# DBoard_Conn.net
KiCad netlist of a schematic drawn in Altium Designer
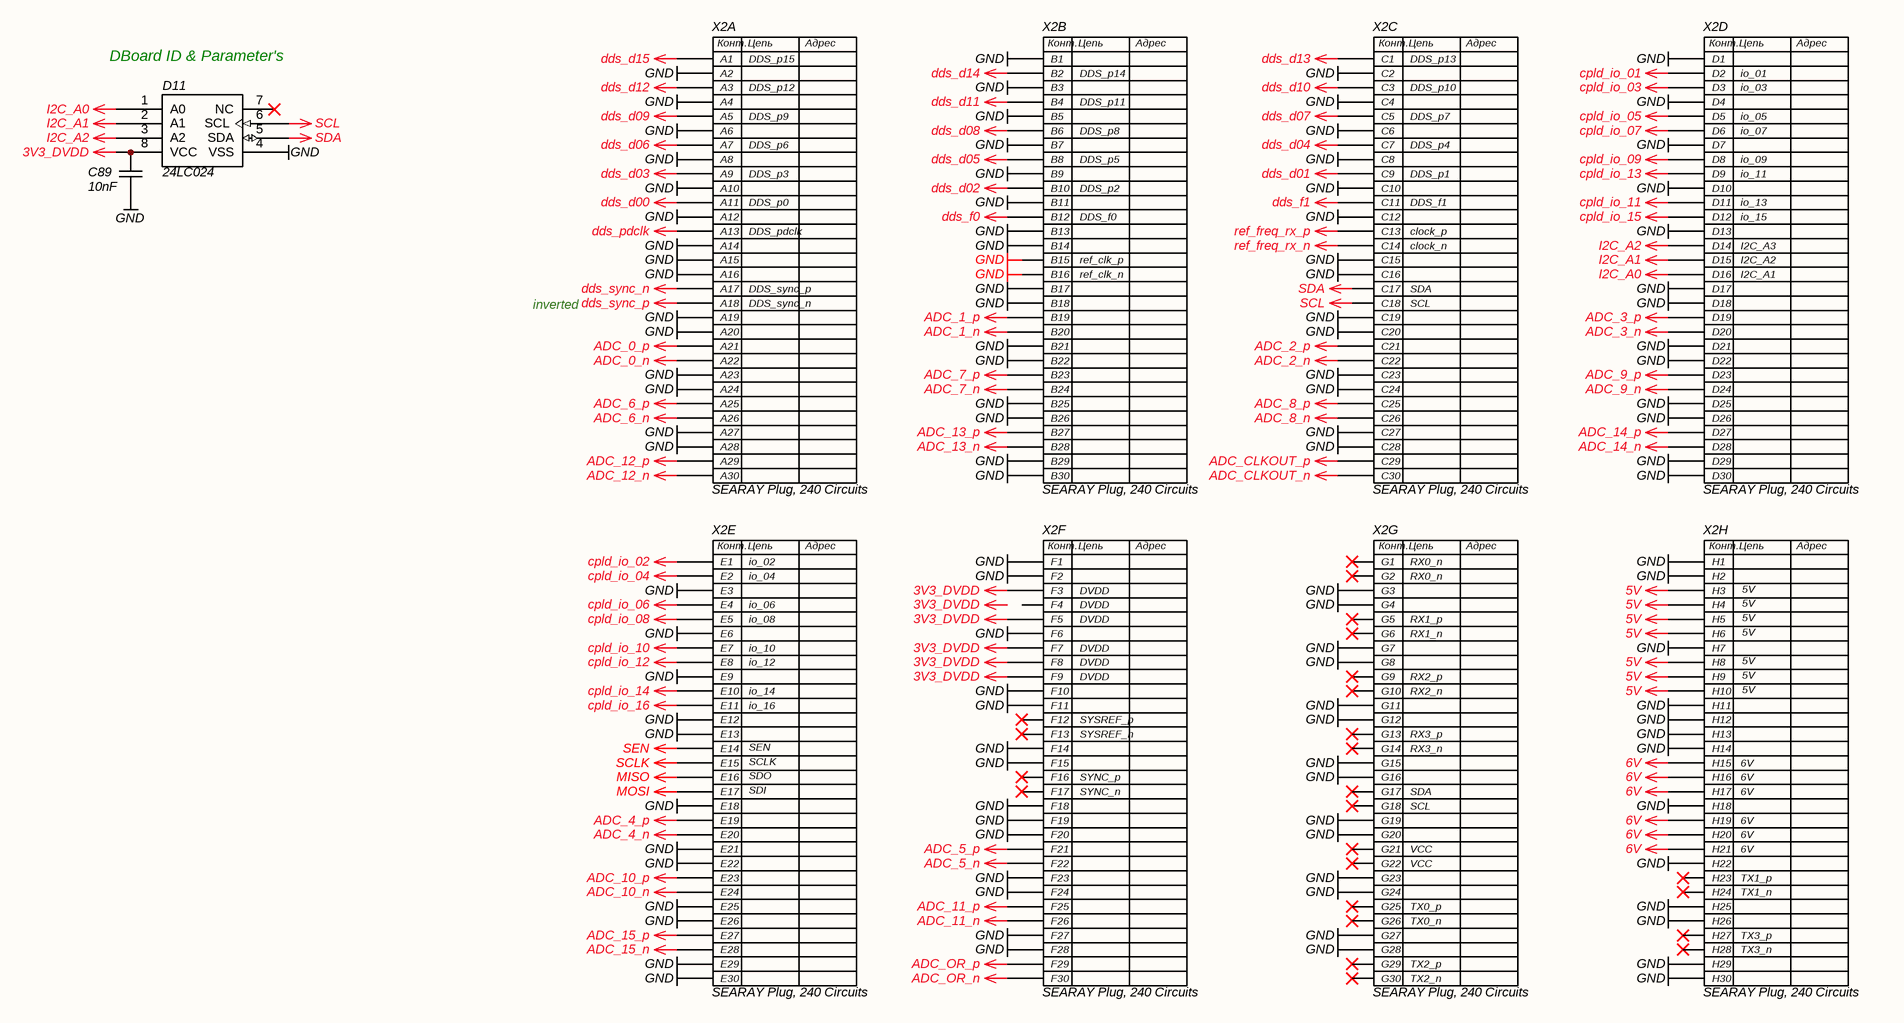
[diagram p0: DBoard_Conn.SchDoc]

(export (version "E")
  (design (tool "Eeschema 10.0.6"))
  (components
    (comp (ref "C89")
      (value "10nF")
      (footprint "C0402")
      (description "SMD Capacitor")
      (fields (field (name "MANUFACTURER") "Murata") (field (name "TOLERANCE") "10%"))
      (libsource (lib "Kintex_SDR") (part "CAP"))
    )
    (comp (ref "D11")
      (value "24LC024")
      (footprint "SOIC_SN8")
      (description "I2C EEPROM")
      (fields (field (name "MANUFACTURER") "Microchip") (field (name "VOLTAGE") "2.5-5.5V"))
      (libsource (lib "Kintex_SDR") (part "24LC024"))
    )
    (comp (ref "X2")
      (value "SEARAY Plug, 240 Circuits")
      (footprint "DBLib:Molex_459703185")
      (description "1.27mm Pitch, SEARAY Plug, 240 Circuits, 2.00mm Unmated Height, 8 Rows, with Pegs")
      (fields (field (name "MANUFACTURER") "Molex"))
      (libsource (lib "DBLib") (part "Molex_SEARAY™ 45970"))
    )
  )
  (nets
    (net (code "42") (name "3V3_DVDD") (class "Default")
      (node (ref "C89") (pin "2") (pinfunction "2_2") (pintype "passive"))
      (node (ref "D11") (pin "8") (pinfunction "VCC_8") (pintype "power_in"))
      (node (ref "X2") (pin "F3") (pinfunction "F3_F3") (pintype "passive"))
      (node (ref "X2") (pin "F5") (pinfunction "F5_F5") (pintype "passive"))
      (node (ref "X2") (pin "F7") (pinfunction "F7_F7") (pintype "passive"))
      (node (ref "X2") (pin "F8") (pinfunction "F8_F8") (pintype "passive"))
      (node (ref "X2") (pin "F9") (pinfunction "F9_F9") (pintype "passive"))
    )
    (net (code "43") (name "5V") (class "Default")
      (node (ref "X2") (pin "H10") (pinfunction "H10_H10") (pintype "passive"))
      (node (ref "X2") (pin "H3") (pinfunction "H3_H3") (pintype "passive"))
      (node (ref "X2") (pin "H4") (pinfunction "H4_H4") (pintype "passive"))
      (node (ref "X2") (pin "H5") (pinfunction "H5_H5") (pintype "passive"))
      (node (ref "X2") (pin "H6") (pinfunction "H6_H6") (pintype "passive"))
      (node (ref "X2") (pin "H8") (pinfunction "H8_H8") (pintype "passive"))
      (node (ref "X2") (pin "H9") (pinfunction "H9_H9") (pintype "passive"))
    )
    (net (code "44") (name "6V") (class "Default")
      (node (ref "X2") (pin "H15") (pinfunction "H15_H15") (pintype "passive"))
      (node (ref "X2") (pin "H16") (pinfunction "H16_H16") (pintype "passive"))
      (node (ref "X2") (pin "H17") (pinfunction "H17_H17") (pintype "passive"))
      (node (ref "X2") (pin "H19") (pinfunction "H19_H19") (pintype "passive"))
      (node (ref "X2") (pin "H20") (pinfunction "H20_H20") (pintype "passive"))
      (node (ref "X2") (pin "H21") (pinfunction "H21_H21") (pintype "passive"))
    )
    (net (code "45") (name "ADC_0_n") (class "Default")
      (node (ref "X2") (pin "A22") (pinfunction "A22_A22") (pintype "passive"))
    )
    (net (code "46") (name "ADC_0_p") (class "Default")
      (node (ref "X2") (pin "A21") (pinfunction "A21_A21") (pintype "passive"))
    )
    (net (code "47") (name "ADC_1_n") (class "Default")
      (node (ref "X2") (pin "B20") (pinfunction "B20_B20") (pintype "passive"))
    )
    (net (code "48") (name "ADC_1_p") (class "Default")
      (node (ref "X2") (pin "B19") (pinfunction "B19_B19") (pintype "passive"))
    )
    (net (code "49") (name "ADC_2_n") (class "Default")
      (node (ref "X2") (pin "C22") (pinfunction "C22_C22") (pintype "passive"))
    )
    (net (code "50") (name "ADC_2_p") (class "Default")
      (node (ref "X2") (pin "C21") (pinfunction "C21_C21") (pintype "passive"))
    )
    (net (code "51") (name "ADC_3_n") (class "Default")
      (node (ref "X2") (pin "D20") (pinfunction "D20_D20") (pintype "passive"))
    )
    (net (code "52") (name "ADC_3_p") (class "Default")
      (node (ref "X2") (pin "D19") (pinfunction "D19_D19") (pintype "passive"))
    )
    (net (code "53") (name "ADC_4_n") (class "Default")
      (node (ref "X2") (pin "E20") (pinfunction "E20_E20") (pintype "passive"))
    )
    (net (code "54") (name "ADC_4_p") (class "Default")
      (node (ref "X2") (pin "E19") (pinfunction "E19_E19") (pintype "passive"))
    )
    (net (code "55") (name "ADC_5_n") (class "Default")
      (node (ref "X2") (pin "F22") (pinfunction "F22_F22") (pintype "passive"))
    )
    (net (code "56") (name "ADC_5_p") (class "Default")
      (node (ref "X2") (pin "F21") (pinfunction "F21_F21") (pintype "passive"))
    )
    (net (code "57") (name "ADC_6_n") (class "Default")
      (node (ref "X2") (pin "A26") (pinfunction "A26_A26") (pintype "passive"))
    )
    (net (code "58") (name "ADC_6_p") (class "Default")
      (node (ref "X2") (pin "A25") (pinfunction "A25_A25") (pintype "passive"))
    )
    (net (code "59") (name "ADC_7_n") (class "Default")
      (node (ref "X2") (pin "B24") (pinfunction "B24_B24") (pintype "passive"))
    )
    (net (code "60") (name "ADC_7_p") (class "Default")
      (node (ref "X2") (pin "B23") (pinfunction "B23_B23") (pintype "passive"))
    )
    (net (code "61") (name "ADC_8_n") (class "Default")
      (node (ref "X2") (pin "C26") (pinfunction "C26_C26") (pintype "passive"))
    )
    (net (code "62") (name "ADC_8_p") (class "Default")
      (node (ref "X2") (pin "C25") (pinfunction "C25_C25") (pintype "passive"))
    )
    (net (code "63") (name "ADC_9_n") (class "Default")
      (node (ref "X2") (pin "D24") (pinfunction "D24_D24") (pintype "passive"))
    )
    (net (code "64") (name "ADC_9_p") (class "Default")
      (node (ref "X2") (pin "D23") (pinfunction "D23_D23") (pintype "passive"))
    )
    (net (code "65") (name "ADC_10_n") (class "Default")
      (node (ref "X2") (pin "E24") (pinfunction "E24_E24") (pintype "passive"))
    )
    (net (code "66") (name "ADC_10_p") (class "Default")
      (node (ref "X2") (pin "E23") (pinfunction "E23_E23") (pintype "passive"))
    )
    (net (code "67") (name "ADC_11_n") (class "Default")
      (node (ref "X2") (pin "F26") (pinfunction "F26_F26") (pintype "passive"))
    )
    (net (code "68") (name "ADC_11_p") (class "Default")
      (node (ref "X2") (pin "F25") (pinfunction "F25_F25") (pintype "passive"))
    )
    (net (code "69") (name "ADC_12_n") (class "Default")
      (node (ref "X2") (pin "A30") (pinfunction "A30_A30") (pintype "passive"))
    )
    (net (code "70") (name "ADC_12_p") (class "Default")
      (node (ref "X2") (pin "A29") (pinfunction "A29_A29") (pintype "passive"))
    )
    (net (code "71") (name "ADC_13_n") (class "Default")
      (node (ref "X2") (pin "B28") (pinfunction "B28_B28") (pintype "passive"))
    )
    (net (code "72") (name "ADC_13_p") (class "Default")
      (node (ref "X2") (pin "B27") (pinfunction "B27_B27") (pintype "passive"))
    )
    (net (code "73") (name "ADC_14_n") (class "Default")
      (node (ref "X2") (pin "D28") (pinfunction "D28_D28") (pintype "passive"))
    )
    (net (code "74") (name "ADC_14_p") (class "Default")
      (node (ref "X2") (pin "D27") (pinfunction "D27_D27") (pintype "passive"))
    )
    (net (code "75") (name "ADC_15_n") (class "Default")
      (node (ref "X2") (pin "E28") (pinfunction "E28_E28") (pintype "passive"))
    )
    (net (code "76") (name "ADC_15_p") (class "Default")
      (node (ref "X2") (pin "E27") (pinfunction "E27_E27") (pintype "passive"))
    )
    (net (code "77") (name "ADC_CLKOUT_n") (class "Default")
      (node (ref "X2") (pin "C30") (pinfunction "C30_C30") (pintype "passive"))
    )
    (net (code "78") (name "ADC_CLKOUT_p") (class "Default")
      (node (ref "X2") (pin "C29") (pinfunction "C29_C29") (pintype "passive"))
    )
    (net (code "79") (name "ADC_OR_n") (class "Default")
      (node (ref "X2") (pin "F30") (pinfunction "F30_F30") (pintype "passive"))
    )
    (net (code "80") (name "ADC_OR_p") (class "Default")
      (node (ref "X2") (pin "F29") (pinfunction "F29_F29") (pintype "passive"))
    )
    (net (code "81") (name "GND") (class "Default")
      (node (ref "C89") (pin "1") (pinfunction "1_1") (pintype "passive"))
      (node (ref "D11") (pin "4") (pinfunction "VSS_4") (pintype "power_in"))
      (node (ref "X2") (pin "A10") (pinfunction "A10_A10") (pintype "passive"))
      (node (ref "X2") (pin "A12") (pinfunction "A12_A12") (pintype "passive"))
      (node (ref "X2") (pin "A14") (pinfunction "A14_A14") (pintype "passive"))
      (node (ref "X2") (pin "A15") (pinfunction "A15_A15") (pintype "passive"))
      (node (ref "X2") (pin "A16") (pinfunction "A16_A16") (pintype "passive"))
      (node (ref "X2") (pin "A19") (pinfunction "A19_A19") (pintype "passive"))
      (node (ref "X2") (pin "A2") (pinfunction "A2_A2") (pintype "passive"))
      (node (ref "X2") (pin "A20") (pinfunction "A20_A20") (pintype "passive"))
      (node (ref "X2") (pin "A23") (pinfunction "A23_A23") (pintype "passive"))
      (node (ref "X2") (pin "A24") (pinfunction "A24_A24") (pintype "passive"))
      (node (ref "X2") (pin "A27") (pinfunction "A27_A27") (pintype "passive"))
      (node (ref "X2") (pin "A28") (pinfunction "A28_A28") (pintype "passive"))
      (node (ref "X2") (pin "A4") (pinfunction "A4_A4") (pintype "passive"))
      (node (ref "X2") (pin "A6") (pinfunction "A6_A6") (pintype "passive"))
      (node (ref "X2") (pin "A8") (pinfunction "A8_A8") (pintype "passive"))
      (node (ref "X2") (pin "B1") (pinfunction "B1_B1") (pintype "passive"))
      (node (ref "X2") (pin "B11") (pinfunction "B11_B11") (pintype "passive"))
      (node (ref "X2") (pin "B13") (pinfunction "B13_B13") (pintype "passive"))
      (node (ref "X2") (pin "B14") (pinfunction "B14_B14") (pintype "passive"))
      (node (ref "X2") (pin "B15") (pinfunction "B15_B15") (pintype "passive"))
      (node (ref "X2") (pin "B16") (pinfunction "B16_B16") (pintype "passive"))
      (node (ref "X2") (pin "B17") (pinfunction "B17_B17") (pintype "passive"))
      (node (ref "X2") (pin "B18") (pinfunction "B18_B18") (pintype "passive"))
      (node (ref "X2") (pin "B21") (pinfunction "B21_B21") (pintype "passive"))
      (node (ref "X2") (pin "B22") (pinfunction "B22_B22") (pintype "passive"))
      (node (ref "X2") (pin "B25") (pinfunction "B25_B25") (pintype "passive"))
      (node (ref "X2") (pin "B26") (pinfunction "B26_B26") (pintype "passive"))
      (node (ref "X2") (pin "B29") (pinfunction "B29_B29") (pintype "passive"))
      (node (ref "X2") (pin "B3") (pinfunction "B3_B3") (pintype "passive"))
      (node (ref "X2") (pin "B30") (pinfunction "B30_B30") (pintype "passive"))
      (node (ref "X2") (pin "B5") (pinfunction "B5_B5") (pintype "passive"))
      (node (ref "X2") (pin "B7") (pinfunction "B7_B7") (pintype "passive"))
      (node (ref "X2") (pin "B9") (pinfunction "B9_B9") (pintype "passive"))
      (node (ref "X2") (pin "C10") (pinfunction "C10_C10") (pintype "passive"))
      (node (ref "X2") (pin "C12") (pinfunction "C12_C12") (pintype "passive"))
      (node (ref "X2") (pin "C15") (pinfunction "C15_C15") (pintype "passive"))
      (node (ref "X2") (pin "C16") (pinfunction "C16_C16") (pintype "passive"))
      (node (ref "X2") (pin "C19") (pinfunction "C19_C19") (pintype "passive"))
      (node (ref "X2") (pin "C2") (pinfunction "C2_C2") (pintype "passive"))
      (node (ref "X2") (pin "C20") (pinfunction "C20_C20") (pintype "passive"))
      (node (ref "X2") (pin "C23") (pinfunction "C23_C23") (pintype "passive"))
      (node (ref "X2") (pin "C24") (pinfunction "C24_C24") (pintype "passive"))
      (node (ref "X2") (pin "C27") (pinfunction "C27_C27") (pintype "passive"))
      (node (ref "X2") (pin "C28") (pinfunction "C28_C28") (pintype "passive"))
      (node (ref "X2") (pin "C4") (pinfunction "C4_C4") (pintype "passive"))
      (node (ref "X2") (pin "C6") (pinfunction "C6_C6") (pintype "passive"))
      (node (ref "X2") (pin "C8") (pinfunction "C8_C8") (pintype "passive"))
      (node (ref "X2") (pin "D1") (pinfunction "D1_D1") (pintype "passive"))
      (node (ref "X2") (pin "D10") (pinfunction "D10_D10") (pintype "passive"))
      (node (ref "X2") (pin "D13") (pinfunction "D13_D13") (pintype "passive"))
      (node (ref "X2") (pin "D17") (pinfunction "D17_D17") (pintype "passive"))
      (node (ref "X2") (pin "D18") (pinfunction "D18_D18") (pintype "passive"))
      (node (ref "X2") (pin "D21") (pinfunction "D21_D21") (pintype "passive"))
      (node (ref "X2") (pin "D22") (pinfunction "D22_D22") (pintype "passive"))
      (node (ref "X2") (pin "D25") (pinfunction "D25_D25") (pintype "passive"))
      (node (ref "X2") (pin "D26") (pinfunction "D26_D26") (pintype "passive"))
      (node (ref "X2") (pin "D29") (pinfunction "D29_D29") (pintype "passive"))
      (node (ref "X2") (pin "D30") (pinfunction "D30_D30") (pintype "passive"))
      (node (ref "X2") (pin "D4") (pinfunction "D4_D4") (pintype "passive"))
      (node (ref "X2") (pin "D7") (pinfunction "D7_D7") (pintype "passive"))
      (node (ref "X2") (pin "E12") (pinfunction "E12_E12") (pintype "passive"))
      (node (ref "X2") (pin "E13") (pinfunction "E13_E13") (pintype "passive"))
      (node (ref "X2") (pin "E18") (pinfunction "E18_E18") (pintype "passive"))
      (node (ref "X2") (pin "E21") (pinfunction "E21_E21") (pintype "passive"))
      (node (ref "X2") (pin "E22") (pinfunction "E22_E22") (pintype "passive"))
      (node (ref "X2") (pin "E25") (pinfunction "E25_E25") (pintype "passive"))
      (node (ref "X2") (pin "E26") (pinfunction "E26_E26") (pintype "passive"))
      (node (ref "X2") (pin "E29") (pinfunction "E29_E29") (pintype "passive"))
      (node (ref "X2") (pin "E3") (pinfunction "E3_E3") (pintype "passive"))
      (node (ref "X2") (pin "E30") (pinfunction "E30_E30") (pintype "passive"))
      (node (ref "X2") (pin "E6") (pinfunction "E6_E6") (pintype "passive"))
      (node (ref "X2") (pin "E9") (pinfunction "E9_E9") (pintype "passive"))
      (node (ref "X2") (pin "F1") (pinfunction "F1_F1") (pintype "passive"))
      (node (ref "X2") (pin "F10") (pinfunction "F10_F10") (pintype "passive"))
      (node (ref "X2") (pin "F11") (pinfunction "F11_F11") (pintype "passive"))
      (node (ref "X2") (pin "F14") (pinfunction "F14_F14") (pintype "passive"))
      (node (ref "X2") (pin "F15") (pinfunction "F15_F15") (pintype "passive"))
      (node (ref "X2") (pin "F18") (pinfunction "F18_F18") (pintype "passive"))
      (node (ref "X2") (pin "F19") (pinfunction "F19_F19") (pintype "passive"))
      (node (ref "X2") (pin "F2") (pinfunction "F2_F2") (pintype "passive"))
      (node (ref "X2") (pin "F20") (pinfunction "F20_F20") (pintype "passive"))
      (node (ref "X2") (pin "F23") (pinfunction "F23_F23") (pintype "passive"))
      (node (ref "X2") (pin "F24") (pinfunction "F24_F24") (pintype "passive"))
      (node (ref "X2") (pin "F27") (pinfunction "F27_F27") (pintype "passive"))
      (node (ref "X2") (pin "F28") (pinfunction "F28_F28") (pintype "passive"))
      (node (ref "X2") (pin "F6") (pinfunction "F6_F6") (pintype "passive"))
      (node (ref "X2") (pin "G11") (pinfunction "G11_G11") (pintype "passive"))
      (node (ref "X2") (pin "G12") (pinfunction "G12_G12") (pintype "passive"))
      (node (ref "X2") (pin "G15") (pinfunction "G15_G15") (pintype "passive"))
      (node (ref "X2") (pin "G16") (pinfunction "G16_G16") (pintype "passive"))
      (node (ref "X2") (pin "G19") (pinfunction "G19_G19") (pintype "passive"))
      (node (ref "X2") (pin "G20") (pinfunction "G20_G20") (pintype "passive"))
      (node (ref "X2") (pin "G23") (pinfunction "G23_G23") (pintype "passive"))
      (node (ref "X2") (pin "G24") (pinfunction "G24_G24") (pintype "passive"))
      (node (ref "X2") (pin "G27") (pinfunction "G27_G27") (pintype "passive"))
      (node (ref "X2") (pin "G28") (pinfunction "G28_G28") (pintype "passive"))
      (node (ref "X2") (pin "G3") (pinfunction "G3_G3") (pintype "passive"))
      (node (ref "X2") (pin "G4") (pinfunction "G4_G4") (pintype "passive"))
      (node (ref "X2") (pin "G7") (pinfunction "G7_G7") (pintype "passive"))
      (node (ref "X2") (pin "G8") (pinfunction "G8_G8") (pintype "passive"))
      (node (ref "X2") (pin "H1") (pinfunction "H1_H1") (pintype "passive"))
      (node (ref "X2") (pin "H11") (pinfunction "H11_H11") (pintype "passive"))
      (node (ref "X2") (pin "H12") (pinfunction "H12_H12") (pintype "passive"))
      (node (ref "X2") (pin "H13") (pinfunction "H13_H13") (pintype "passive"))
      (node (ref "X2") (pin "H14") (pinfunction "H14_H14") (pintype "passive"))
      (node (ref "X2") (pin "H18") (pinfunction "H18_H18") (pintype "passive"))
      (node (ref "X2") (pin "H2") (pinfunction "H2_H2") (pintype "passive"))
      (node (ref "X2") (pin "H22") (pinfunction "H22_H22") (pintype "passive"))
      (node (ref "X2") (pin "H25") (pinfunction "H25_H25") (pintype "passive"))
      (node (ref "X2") (pin "H26") (pinfunction "H26_H26") (pintype "passive"))
      (node (ref "X2") (pin "H29") (pinfunction "H29_H29") (pintype "passive"))
      (node (ref "X2") (pin "H30") (pinfunction "H30_H30") (pintype "passive"))
      (node (ref "X2") (pin "H7") (pinfunction "H7_H7") (pintype "passive"))
    )
    (net (code "82") (name "I2C_A0") (class "Default")
      (node (ref "D11") (pin "1") (pinfunction "A0_1") (pintype "passive"))
      (node (ref "X2") (pin "D16") (pinfunction "D16_D16") (pintype "passive"))
    )
    (net (code "83") (name "I2C_A1") (class "Default")
      (node (ref "D11") (pin "2") (pinfunction "A1_2") (pintype "passive"))
      (node (ref "X2") (pin "D15") (pinfunction "D15_D15") (pintype "passive"))
    )
    (net (code "84") (name "I2C_A2") (class "Default")
      (node (ref "D11") (pin "3") (pinfunction "A2_3") (pintype "passive"))
      (node (ref "X2") (pin "D14") (pinfunction "D14_D14") (pintype "passive"))
    )
    (net (code "85") (name "MISO") (class "Default")
      (node (ref "X2") (pin "E16") (pinfunction "E16_E16") (pintype "passive"))
    )
    (net (code "86") (name "MOSI") (class "Default")
      (node (ref "X2") (pin "E17") (pinfunction "E17_E17") (pintype "passive"))
    )
    (net (code "87") (name "SCL") (class "Default")
      (node (ref "D11") (pin "6") (pinfunction "SCL_6") (pintype "input"))
      (node (ref "X2") (pin "C18") (pinfunction "C18_C18") (pintype "passive"))
    )
    (net (code "88") (name "SCLK") (class "Default")
      (node (ref "X2") (pin "E15") (pinfunction "E15_E15") (pintype "passive"))
    )
    (net (code "89") (name "SDA") (class "Default")
      (node (ref "D11") (pin "5") (pinfunction "SDA_5") (pintype "bidirectional"))
      (node (ref "X2") (pin "C17") (pinfunction "C17_C17") (pintype "passive"))
    )
    (net (code "90") (name "SEN") (class "Default")
      (node (ref "X2") (pin "E14") (pinfunction "E14_E14") (pintype "passive"))
    )
    (net (code "91") (name "cpld_io_01") (class "Default")
      (node (ref "X2") (pin "D2") (pinfunction "D2_D2") (pintype "passive"))
    )
    (net (code "92") (name "cpld_io_02") (class "Default")
      (node (ref "X2") (pin "E1") (pinfunction "E1_E1") (pintype "passive"))
    )
    (net (code "93") (name "cpld_io_03") (class "Default")
      (node (ref "X2") (pin "D3") (pinfunction "D3_D3") (pintype "passive"))
    )
    (net (code "94") (name "cpld_io_04") (class "Default")
      (node (ref "X2") (pin "E2") (pinfunction "E2_E2") (pintype "passive"))
    )
    (net (code "95") (name "cpld_io_05") (class "Default")
      (node (ref "X2") (pin "D5") (pinfunction "D5_D5") (pintype "passive"))
    )
    (net (code "96") (name "cpld_io_06") (class "Default")
      (node (ref "X2") (pin "E4") (pinfunction "E4_E4") (pintype "passive"))
    )
    (net (code "97") (name "cpld_io_07") (class "Default")
      (node (ref "X2") (pin "D6") (pinfunction "D6_D6") (pintype "passive"))
    )
    (net (code "98") (name "cpld_io_08") (class "Default")
      (node (ref "X2") (pin "E5") (pinfunction "E5_E5") (pintype "passive"))
    )
    (net (code "99") (name "cpld_io_09") (class "Default")
      (node (ref "X2") (pin "D8") (pinfunction "D8_D8") (pintype "passive"))
    )
    (net (code "100") (name "cpld_io_10") (class "Default")
      (node (ref "X2") (pin "E7") (pinfunction "E7_E7") (pintype "passive"))
    )
    (net (code "101") (name "cpld_io_11") (class "Default")
      (node (ref "X2") (pin "D11") (pinfunction "D11_D11") (pintype "passive"))
    )
    (net (code "102") (name "cpld_io_12") (class "Default")
      (node (ref "X2") (pin "E8") (pinfunction "E8_E8") (pintype "passive"))
    )
    (net (code "103") (name "cpld_io_13") (class "Default")
      (node (ref "X2") (pin "D9") (pinfunction "D9_D9") (pintype "passive"))
    )
    (net (code "104") (name "cpld_io_14") (class "Default")
      (node (ref "X2") (pin "E10") (pinfunction "E10_E10") (pintype "passive"))
    )
    (net (code "105") (name "cpld_io_15") (class "Default")
      (node (ref "X2") (pin "D12") (pinfunction "D12_D12") (pintype "passive"))
    )
    (net (code "106") (name "cpld_io_16") (class "Default")
      (node (ref "X2") (pin "E11") (pinfunction "E11_E11") (pintype "passive"))
    )
    (net (code "107") (name "dds_d00") (class "Default")
      (node (ref "X2") (pin "A11") (pinfunction "A11_A11") (pintype "passive"))
    )
    (net (code "108") (name "dds_d01") (class "Default")
      (node (ref "X2") (pin "C9") (pinfunction "C9_C9") (pintype "passive"))
    )
    (net (code "109") (name "dds_d02") (class "Default")
      (node (ref "X2") (pin "B10") (pinfunction "B10_B10") (pintype "passive"))
    )
    (net (code "110") (name "dds_d03") (class "Default")
      (node (ref "X2") (pin "A9") (pinfunction "A9_A9") (pintype "passive"))
    )
    (net (code "111") (name "dds_d04") (class "Default")
      (node (ref "X2") (pin "C7") (pinfunction "C7_C7") (pintype "passive"))
    )
    (net (code "112") (name "dds_d05") (class "Default")
      (node (ref "X2") (pin "B8") (pinfunction "B8_B8") (pintype "passive"))
    )
    (net (code "113") (name "dds_d06") (class "Default")
      (node (ref "X2") (pin "A7") (pinfunction "A7_A7") (pintype "passive"))
    )
    (net (code "114") (name "dds_d07") (class "Default")
      (node (ref "X2") (pin "C5") (pinfunction "C5_C5") (pintype "passive"))
    )
    (net (code "115") (name "dds_d08") (class "Default")
      (node (ref "X2") (pin "B6") (pinfunction "B6_B6") (pintype "passive"))
    )
    (net (code "116") (name "dds_d09") (class "Default")
      (node (ref "X2") (pin "A5") (pinfunction "A5_A5") (pintype "passive"))
    )
    (net (code "117") (name "dds_d10") (class "Default")
      (node (ref "X2") (pin "C3") (pinfunction "C3_C3") (pintype "passive"))
    )
    (net (code "118") (name "dds_d11") (class "Default")
      (node (ref "X2") (pin "B4") (pinfunction "B4_B4") (pintype "passive"))
    )
    (net (code "119") (name "dds_d12") (class "Default")
      (node (ref "X2") (pin "A3") (pinfunction "A3_A3") (pintype "passive"))
    )
    (net (code "120") (name "dds_d13") (class "Default")
      (node (ref "X2") (pin "C1") (pinfunction "C1_C1") (pintype "passive"))
    )
    (net (code "121") (name "dds_d14") (class "Default")
      (node (ref "X2") (pin "B2") (pinfunction "B2_B2") (pintype "passive"))
    )
    (net (code "122") (name "dds_d15") (class "Default")
      (node (ref "X2") (pin "A1") (pinfunction "A1_A1") (pintype "passive"))
    )
    (net (code "123") (name "dds_f0") (class "Default")
      (node (ref "X2") (pin "B12") (pinfunction "B12_B12") (pintype "passive"))
    )
    (net (code "124") (name "dds_f1") (class "Default")
      (node (ref "X2") (pin "C11") (pinfunction "C11_C11") (pintype "passive"))
    )
    (net (code "125") (name "dds_pdclk") (class "Default")
      (node (ref "X2") (pin "A13") (pinfunction "A13_A13") (pintype "passive"))
    )
    (net (code "126") (name "dds_sync_n") (class "Default")
      (node (ref "X2") (pin "A17") (pinfunction "A17_A17") (pintype "passive"))
    )
    (net (code "127") (name "dds_sync_p") (class "Default")
      (node (ref "X2") (pin "A18") (pinfunction "A18_A18") (pintype "passive"))
    )
    (net (code "128") (name "ref_freq_rx_n") (class "Default")
      (node (ref "X2") (pin "C14") (pinfunction "C14_C14") (pintype "passive"))
    )
    (net (code "129") (name "ref_freq_rx_p") (class "Default")
      (node (ref "X2") (pin "C13") (pinfunction "C13_C13") (pintype "passive"))
    )
    (net (code "130") (name "unconnected-(D11-NC-Pad7)") (class "Default")
      (node (ref "D11") (pin "7") (pinfunction "NC_7") (pintype "passive+no_connect"))
    )
    (net (code "131") (name "unconnected-(X2-PadF4)") (class "Default")
      (node (ref "X2") (pin "F4") (pinfunction "F4_F4") (pintype "passive"))
    )
    (net (code "132") (name "unconnected-(X2-PadF12)") (class "Default")
      (node (ref "X2") (pin "F12") (pinfunction "F12_F12") (pintype "passive+no_connect"))
    )
    (net (code "133") (name "unconnected-(X2-PadF13)") (class "Default")
      (node (ref "X2") (pin "F13") (pinfunction "F13_F13") (pintype "passive+no_connect"))
    )
    (net (code "134") (name "unconnected-(X2-PadF16)") (class "Default")
      (node (ref "X2") (pin "F16") (pinfunction "F16_F16") (pintype "passive+no_connect"))
    )
    (net (code "135") (name "unconnected-(X2-PadF17)") (class "Default")
      (node (ref "X2") (pin "F17") (pinfunction "F17_F17") (pintype "passive+no_connect"))
    )
    (net (code "136") (name "unconnected-(X2-PadG1)") (class "Default")
      (node (ref "X2") (pin "G1") (pinfunction "G1_G1") (pintype "passive+no_connect"))
    )
    (net (code "137") (name "unconnected-(X2-PadG2)") (class "Default")
      (node (ref "X2") (pin "G2") (pinfunction "G2_G2") (pintype "passive+no_connect"))
    )
    (net (code "138") (name "unconnected-(X2-PadG5)") (class "Default")
      (node (ref "X2") (pin "G5") (pinfunction "G5_G5") (pintype "passive+no_connect"))
    )
    (net (code "139") (name "unconnected-(X2-PadG6)") (class "Default")
      (node (ref "X2") (pin "G6") (pinfunction "G6_G6") (pintype "passive+no_connect"))
    )
    (net (code "140") (name "unconnected-(X2-PadG9)") (class "Default")
      (node (ref "X2") (pin "G9") (pinfunction "G9_G9") (pintype "passive+no_connect"))
    )
    (net (code "141") (name "unconnected-(X2-PadG10)") (class "Default")
      (node (ref "X2") (pin "G10") (pinfunction "G10_G10") (pintype "passive+no_connect"))
    )
    (net (code "142") (name "unconnected-(X2-PadG13)") (class "Default")
      (node (ref "X2") (pin "G13") (pinfunction "G13_G13") (pintype "passive+no_connect"))
    )
    (net (code "143") (name "unconnected-(X2-PadG14)") (class "Default")
      (node (ref "X2") (pin "G14") (pinfunction "G14_G14") (pintype "passive+no_connect"))
    )
    (net (code "144") (name "unconnected-(X2-PadG17)") (class "Default")
      (node (ref "X2") (pin "G17") (pinfunction "G17_G17") (pintype "passive+no_connect"))
    )
    (net (code "145") (name "unconnected-(X2-PadG18)") (class "Default")
      (node (ref "X2") (pin "G18") (pinfunction "G18_G18") (pintype "passive+no_connect"))
    )
    (net (code "146") (name "unconnected-(X2-PadG21)") (class "Default")
      (node (ref "X2") (pin "G21") (pinfunction "G21_G21") (pintype "passive+no_connect"))
    )
    (net (code "147") (name "unconnected-(X2-PadG22)") (class "Default")
      (node (ref "X2") (pin "G22") (pinfunction "G22_G22") (pintype "passive+no_connect"))
    )
    (net (code "148") (name "unconnected-(X2-PadG25)") (class "Default")
      (node (ref "X2") (pin "G25") (pinfunction "G25_G25") (pintype "passive+no_connect"))
    )
    (net (code "149") (name "unconnected-(X2-PadG26)") (class "Default")
      (node (ref "X2") (pin "G26") (pinfunction "G26_G26") (pintype "passive+no_connect"))
    )
    (net (code "150") (name "unconnected-(X2-PadG29)") (class "Default")
      (node (ref "X2") (pin "G29") (pinfunction "G29_G29") (pintype "passive+no_connect"))
    )
    (net (code "151") (name "unconnected-(X2-PadG30)") (class "Default")
      (node (ref "X2") (pin "G30") (pinfunction "G30_G30") (pintype "passive+no_connect"))
    )
    (net (code "152") (name "unconnected-(X2-PadH23)") (class "Default")
      (node (ref "X2") (pin "H23") (pinfunction "H23_H23") (pintype "passive+no_connect"))
    )
    (net (code "153") (name "unconnected-(X2-PadH24)") (class "Default")
      (node (ref "X2") (pin "H24") (pinfunction "H24_H24") (pintype "passive+no_connect"))
    )
    (net (code "154") (name "unconnected-(X2-PadH27)") (class "Default")
      (node (ref "X2") (pin "H27") (pinfunction "H27_H27") (pintype "passive+no_connect"))
    )
    (net (code "155") (name "unconnected-(X2-PadH28)") (class "Default")
      (node (ref "X2") (pin "H28") (pinfunction "H28_H28") (pintype "passive+no_connect"))
    )
  )
)
